# Power.net
KiCad netlist of a schematic drawn in Altium Designer
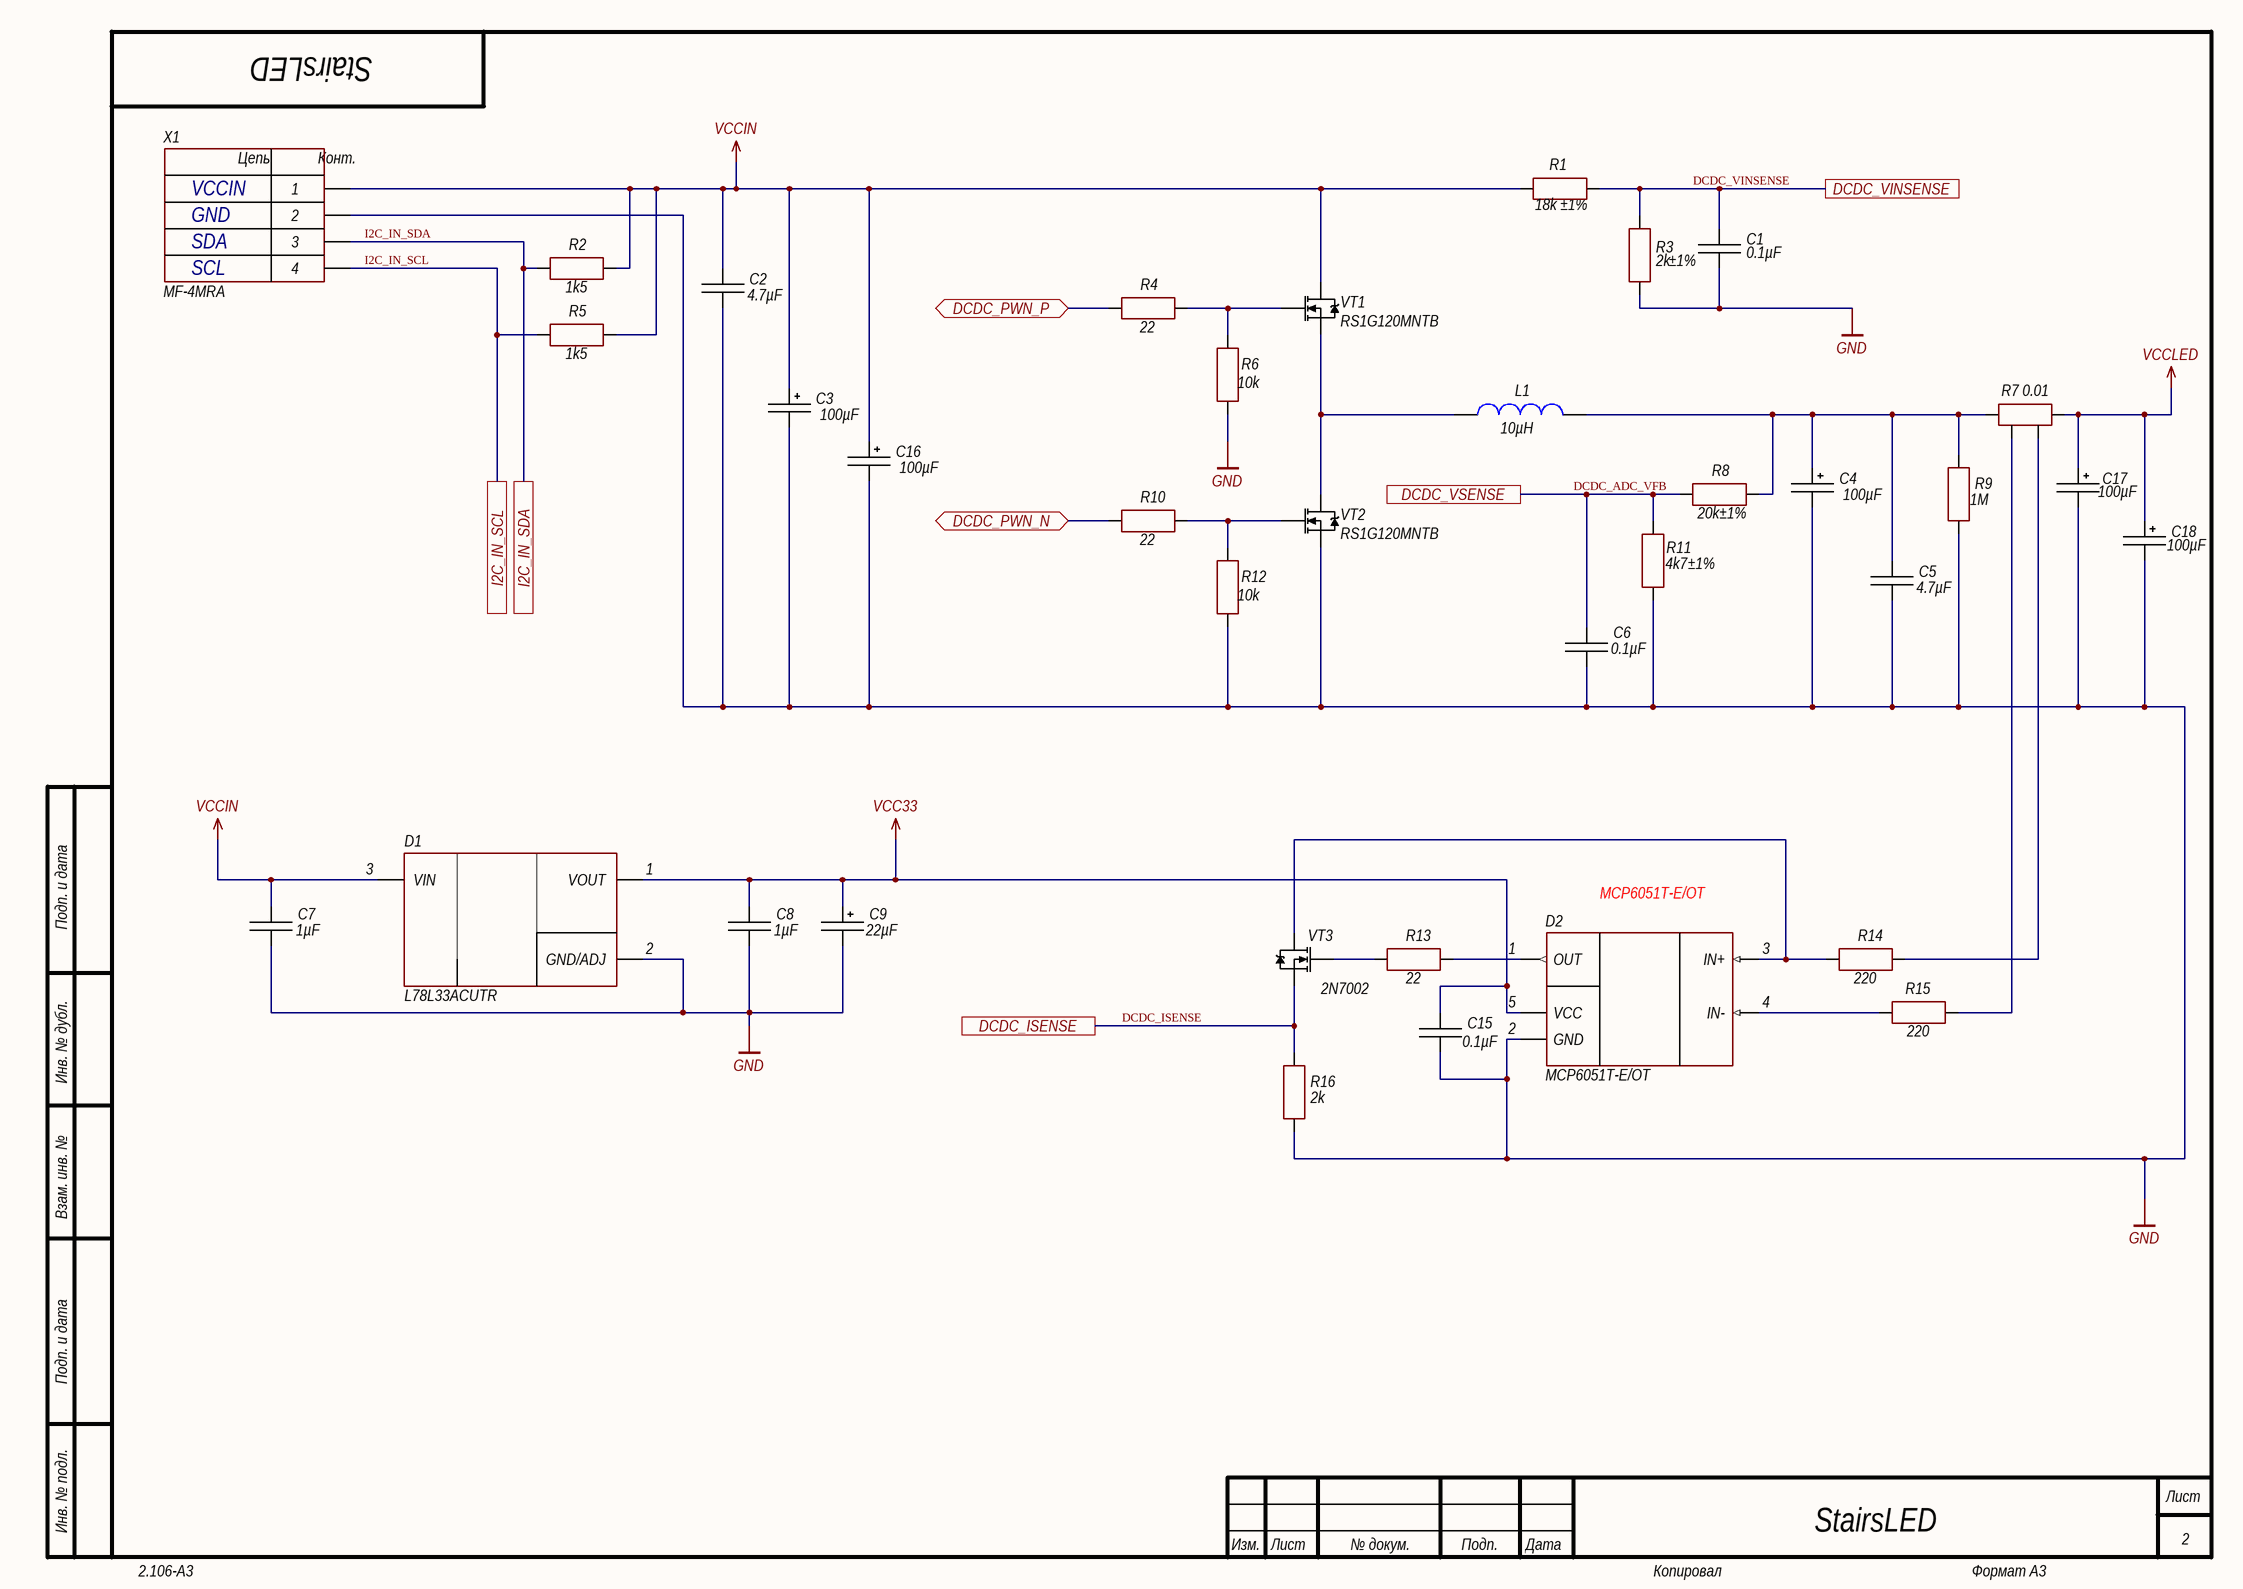
[diagram p0: Power.SchDoc]

(export (version "E")
  (design (tool "Eeschema 10.0.6"))
  (components
    (comp (ref "C1") (value "0.1µF") (footprint "CH0603C") (libsource (lib "Discrete") (part "Capacitor")))
    (comp (ref "C2")
      (value "4.7µF")
      (footprint "CH1206C")
      (fields (field (name "MANUFACTURER") "Murata"))
      (libsource (lib "Discrete") (part "Capacitor"))
    )
    (comp (ref "C3")
      (value "100µF")
      (footprint "D6.3C2.5H11")
      (fields (field (name "MANUFACTURER") "BURNON"))
      (libsource (lib "Discrete") (part "AlumCap"))
    )
    (comp (ref "C4")
      (value "100µF")
      (footprint "D6.3C2.5H11")
      (fields (field (name "MANUFACTURER") "BURNON"))
      (libsource (lib "Discrete") (part "AlumCap"))
    )
    (comp (ref "C5")
      (value "4.7µF")
      (footprint "CH1206C")
      (fields (field (name "MANUFACTURER") "Murata"))
      (libsource (lib "Discrete") (part "Capacitor"))
    )
    (comp (ref "C6") (value "0.1µF") (footprint "CH0603C") (libsource (lib "Discrete") (part "Capacitor")))
    (comp (ref "C7")
      (value "1µF")
      (footprint "CH0603C")
      (fields (field (name "MANUFACTURER") "Murata Electronics Inc."))
      (libsource (lib "Discrete") (part "Capacitor"))
    )
    (comp (ref "C8")
      (value "1µF")
      (footprint "CH0603C")
      (fields (field (name "MANUFACTURER") "Murata Electronics Inc."))
      (libsource (lib "Discrete") (part "Capacitor"))
    )
    (comp (ref "C9") (value "22µF") (footprint "TANTAL_B") (libsource (lib "Discrete") (part "TantalCap")))
    (comp (ref "C15") (value "0.1µF") (footprint "CH0603C") (libsource (lib "Discrete") (part "Capacitor")))
    (comp (ref "C16")
      (value "100µF")
      (footprint "D6.3C2.5H11")
      (fields (field (name "MANUFACTURER") "BURNON"))
      (libsource (lib "Discrete") (part "AlumCap"))
    )
    (comp (ref "C17")
      (value "100µF")
      (footprint "D6.3C2.5H11")
      (fields (field (name "MANUFACTURER") "BURNON"))
      (libsource (lib "Discrete") (part "AlumCap"))
    )
    (comp (ref "C18")
      (value "100µF")
      (footprint "D6.3C2.5H11")
      (fields (field (name "MANUFACTURER") "BURNON"))
      (libsource (lib "Discrete") (part "AlumCap"))
    )
    (comp (ref "D1")
      (value "L78L33ACUTR")
      (footprint "SOT89_123")
      (description "Step-down")
      (fields (field (name "MANUFACTURER") "ST Microelectronics"))
      (libsource (lib "Power Supplies") (part "L78LxxACUTR"))
    )
    (comp (ref "D2")
      (value "MCP6051T-E/OT")
      (footprint "SOT23-5")
      (description "OP amplifier")
      (fields (field (name "MANUFACTURER") "Microchip Technology"))
      (libsource (lib "Analog") (part "MCP6001T"))
    )
    (comp (ref "L1")
      (value "10µH")
      (footprint "IND: CDRH127")
      (fields (field (name "MANUFACTURER") "Sumida Electric"))
      (libsource (lib "Discrete") (part "Inductor"))
    )
    (comp (ref "R1")
      (value "18k")
      (footprint "CH0603R")
      (fields (field (name "COMPONENTKIND") "±1%"))
      (libsource (lib "") (part "Resistor_2"))
    )
    (comp (ref "R2") (value "1k5") (footprint "CH0603R") (libsource (lib "Discrete") (part "Resistor")))
    (comp (ref "R3")
      (value "2k")
      (footprint "CH0603R")
      (fields (field (name "COMPONENTKIND") "±1%"))
      (libsource (lib "Discrete") (part "Resistor"))
    )
    (comp (ref "R4") (value "22") (footprint "CH0603R") (libsource (lib "Discrete") (part "Resistor")))
    (comp (ref "R5") (value "1k5") (footprint "CH0603R") (libsource (lib "Discrete") (part "Resistor")))
    (comp (ref "R6") (value "10k") (footprint "CH0603R") (libsource (lib "") (part "Resistor_1")))
    (comp (ref "R7")
      (value "0.01")
      (footprint "SHNT: CRA2512")
      (fields (field (name "MANUFACTURER") "Bourns"))
      (libsource (lib "Discrete") (part "Shunt"))
    )
    (comp (ref "R8")
      (value "20k")
      (footprint "CH0603R")
      (fields (field (name "COMPONENTKIND") "±1%"))
      (libsource (lib "Discrete") (part "Resistor"))
    )
    (comp (ref "R9") (value "1M") (footprint "CH1206R") (libsource (lib "") (part "Resistor_1")))
    (comp (ref "R10") (value "22") (footprint "CH0603R") (libsource (lib "Discrete") (part "Resistor")))
    (comp (ref "R11")
      (value "4k7")
      (footprint "CH0603R")
      (fields (field (name "COMPONENTKIND") "±1%"))
      (libsource (lib "") (part "Resistor_1"))
    )
    (comp (ref "R12") (value "10k") (footprint "CH0603R") (libsource (lib "") (part "Resistor_1")))
    (comp (ref "R13") (value "22") (footprint "CH0603R") (libsource (lib "Discrete") (part "Resistor")))
    (comp (ref "R14") (value "220") (footprint "CH0603R") (libsource (lib "Discrete") (part "Resistor")))
    (comp (ref "R15") (value "220") (footprint "CH0603R") (libsource (lib "Discrete") (part "Resistor")))
    (comp (ref "R16") (value "2k") (footprint "CH0603R") (libsource (lib "") (part "Resistor_1")))
    (comp (ref "VT1")
      (value "RS1G120MNTB")
      (footprint "8-TDSON")
      (description "Mosfet")
      (fields (field (name "MANUFACTURER") "Rohm"))
      (libsource (lib "Transistor") (part "N-chanel"))
    )
    (comp (ref "VT2")
      (value "RS1G120MNTB")
      (footprint "8-TDSON")
      (description "Mosfet")
      (fields (field (name "MANUFACTURER") "Rohm"))
      (libsource (lib "Transistor") (part "N-chanel"))
    )
    (comp (ref "VT3")
      (value "2N7002")
      (footprint "SOT23_132")
      (description "Mosfet")
      (fields (field (name "MANUFACTURER") "ON Semiconductor"))
      (libsource (lib "Transistor") (part "N-chanel"))
    )
    (comp (ref "X1")
      (value "MF-4MRA")
      (footprint "CON: MF-4MRA")
      (libsource (lib "Connectors") (part "4-Connector"))
    )
  )
  (nets
    (net (code "1") (name "/DCDC_ADC_VFB") (class "Default")
      (node (ref "C6") (pin "1") (pinfunction "1_1") (pintype "power_in"))
      (node (ref "R11") (pin "2") (pinfunction "2_2") (pintype "passive"))
      (node (ref "R8") (pin "1") (pinfunction "1_1") (pintype "passive"))
    )
    (net (code "2") (name "/DCDC_ISENSE") (class "Default")
      (node (ref "R16") (pin "2") (pinfunction "2_2") (pintype "passive"))
      (node (ref "VT3") (pin "3") (pinfunction "S_3") (pintype "passive"))
    )
    (net (code "3") (name "/DCDC_PWN_N") (class "Default")
      (node (ref "R10") (pin "1") (pinfunction "1_1") (pintype "passive"))
    )
    (net (code "4") (name "/DCDC_PWN_P") (class "Default")
      (node (ref "R4") (pin "1") (pinfunction "1_1") (pintype "passive"))
    )
    (net (code "5") (name "/DCDC_VINSENSE") (class "Default")
      (node (ref "C1") (pin "1") (pinfunction "1_1") (pintype "power_in"))
      (node (ref "R1") (pin "1") (pinfunction "1_1") (pintype "passive"))
      (node (ref "R3") (pin "2") (pinfunction "2_2") (pintype "passive"))
    )
    (net (code "6") (name "/I2C_IN_SCL") (class "Default")
      (node (ref "R5") (pin "1") (pinfunction "1_1") (pintype "passive"))
      (node (ref "X1") (pin "4") (pinfunction "4_4") (pintype "power_in"))
    )
    (net (code "7") (name "/I2C_IN_SDA") (class "Default")
      (node (ref "R2") (pin "1") (pinfunction "1_1") (pintype "passive"))
      (node (ref "X1") (pin "3") (pinfunction "3_3") (pintype "power_in"))
    )
    (net (code "8") (name "GND") (class "Default")
      (node (ref "C1") (pin "2") (pinfunction "2_2") (pintype "power_in"))
      (node (ref "C15") (pin "1") (pinfunction "1_1") (pintype "power_in"))
      (node (ref "C16") (pin "2") (pinfunction "2_2") (pintype "power_in"))
      (node (ref "C17") (pin "2") (pinfunction "2_2") (pintype "power_in"))
      (node (ref "C18") (pin "2") (pinfunction "2_2") (pintype "power_in"))
      (node (ref "C2") (pin "1") (pinfunction "1_1") (pintype "power_in"))
      (node (ref "C3") (pin "2") (pinfunction "2_2") (pintype "power_in"))
      (node (ref "C4") (pin "2") (pinfunction "2_2") (pintype "power_in"))
      (node (ref "C5") (pin "1") (pinfunction "1_1") (pintype "power_in"))
      (node (ref "C6") (pin "2") (pinfunction "2_2") (pintype "power_in"))
      (node (ref "C7") (pin "1") (pinfunction "1_1") (pintype "power_in"))
      (node (ref "C8") (pin "1") (pinfunction "1_1") (pintype "power_in"))
      (node (ref "C9") (pin "2") (pinfunction "2_2") (pintype "power_in"))
      (node (ref "D1") (pin "2") (pinfunction "GND/ADJ_2") (pintype "power_in"))
      (node (ref "D2") (pin "2") (pinfunction "GND_2") (pintype "power_in"))
      (node (ref "R11") (pin "1") (pinfunction "1_1") (pintype "passive"))
      (node (ref "R12") (pin "1") (pinfunction "1_1") (pintype "passive"))
      (node (ref "R16") (pin "1") (pinfunction "1_1") (pintype "passive"))
      (node (ref "R3") (pin "1") (pinfunction "1_1") (pintype "passive"))
      (node (ref "R6") (pin "1") (pinfunction "1_1") (pintype "passive"))
      (node (ref "R9") (pin "1") (pinfunction "1_1") (pintype "passive"))
      (node (ref "VT2") (pin "3") (pinfunction "S_3") (pintype "passive"))
      (node (ref "X1") (pin "2") (pinfunction "2_2") (pintype "passive"))
    )
    (net (code "9") (name "Net-(C4-Pad1)") (class "Default")
      (node (ref "C4") (pin "1") (pinfunction "1_1") (pintype "power_in"))
      (node (ref "C5") (pin "2") (pinfunction "2_2") (pintype "power_in"))
      (node (ref "L1") (pin "1") (pinfunction "1_1") (pintype "passive"))
      (node (ref "R7") (pin "1") (pinfunction "1_1") (pintype "passive"))
      (node (ref "R8") (pin "2") (pinfunction "2_2") (pintype "passive"))
      (node (ref "R9") (pin "2") (pinfunction "2_2") (pintype "passive"))
    )
    (net (code "10") (name "Net-(D2-IN+)") (class "Default")
      (node (ref "D2") (pin "3") (pinfunction "IN+_3") (pintype "input"))
      (node (ref "R14") (pin "1") (pinfunction "1_1") (pintype "passive"))
      (node (ref "VT3") (pin "2") (pinfunction "D_2") (pintype "passive"))
    )
    (net (code "11") (name "Net-(D2-IN-)") (class "Default")
      (node (ref "D2") (pin "4") (pinfunction "IN-_4") (pintype "input"))
      (node (ref "R15") (pin "1") (pinfunction "1_1") (pintype "passive"))
    )
    (net (code "12") (name "Net-(D2-OUT)") (class "Default")
      (node (ref "D2") (pin "1") (pinfunction "OUT_1") (pintype "output"))
      (node (ref "R13") (pin "2") (pinfunction "2_2") (pintype "passive"))
    )
    (net (code "13") (name "Net-(R14-Pad2)") (class "Default")
      (node (ref "R14") (pin "2") (pinfunction "2_2") (pintype "passive"))
      (node (ref "R7") (pin "4") (pinfunction "4_4") (pintype "passive"))
    )
    (net (code "14") (name "Net-(R15-Pad2)") (class "Default")
      (node (ref "R15") (pin "2") (pinfunction "2_2") (pintype "passive"))
      (node (ref "R7") (pin "3") (pinfunction "3_3") (pintype "passive"))
    )
    (net (code "15") (name "Net-(VT1-G)") (class "Default")
      (node (ref "R4") (pin "2") (pinfunction "2_2") (pintype "passive"))
      (node (ref "R6") (pin "2") (pinfunction "2_2") (pintype "passive"))
      (node (ref "VT1") (pin "1") (pinfunction "G_1") (pintype "passive"))
    )
    (net (code "16") (name "Net-(VT1-S)") (class "Default")
      (node (ref "L1") (pin "2") (pinfunction "2_2") (pintype "passive"))
      (node (ref "VT1") (pin "3") (pinfunction "S_3") (pintype "passive"))
      (node (ref "VT2") (pin "2") (pinfunction "D_2") (pintype "passive"))
    )
    (net (code "17") (name "Net-(VT2-G)") (class "Default")
      (node (ref "R10") (pin "2") (pinfunction "2_2") (pintype "passive"))
      (node (ref "R12") (pin "2") (pinfunction "2_2") (pintype "passive"))
      (node (ref "VT2") (pin "1") (pinfunction "G_1") (pintype "passive"))
    )
    (net (code "18") (name "Net-(VT3-G)") (class "Default")
      (node (ref "R13") (pin "1") (pinfunction "1_1") (pintype "passive"))
      (node (ref "VT3") (pin "1") (pinfunction "G_1") (pintype "passive"))
    )
    (net (code "19") (name "VCC33") (class "Default")
      (node (ref "C15") (pin "2") (pinfunction "2_2") (pintype "power_in"))
      (node (ref "C8") (pin "2") (pinfunction "2_2") (pintype "power_in"))
      (node (ref "C9") (pin "1") (pinfunction "1_1") (pintype "power_in"))
      (node (ref "D1") (pin "1") (pinfunction "VOUT_1") (pintype "power_in"))
      (node (ref "D2") (pin "5") (pinfunction "VCC_5") (pintype "power_in"))
    )
    (net (code "20") (name "VCCIN") (class "Default")
      (node (ref "C16") (pin "1") (pinfunction "1_1") (pintype "power_in"))
      (node (ref "C2") (pin "2") (pinfunction "2_2") (pintype "power_in"))
      (node (ref "C3") (pin "1") (pinfunction "1_1") (pintype "power_in"))
      (node (ref "C7") (pin "2") (pinfunction "2_2") (pintype "power_in"))
      (node (ref "D1") (pin "3") (pinfunction "VIN_3") (pintype "power_in"))
      (node (ref "R1") (pin "2") (pinfunction "2_2") (pintype "passive"))
      (node (ref "R2") (pin "2") (pinfunction "2_2") (pintype "passive"))
      (node (ref "R5") (pin "2") (pinfunction "2_2") (pintype "passive"))
      (node (ref "VT1") (pin "2") (pinfunction "D_2") (pintype "passive"))
      (node (ref "X1") (pin "1") (pinfunction "1_1") (pintype "passive"))
    )
    (net (code "21") (name "VCCLED") (class "Default")
      (node (ref "C17") (pin "1") (pinfunction "1_1") (pintype "power_in"))
      (node (ref "C18") (pin "1") (pinfunction "1_1") (pintype "power_in"))
      (node (ref "R7") (pin "2") (pinfunction "2_2") (pintype "passive"))
    )
  )
)
